# Sens_CC2D.net
KiCad netlist of a schematic drawn in EAGLE
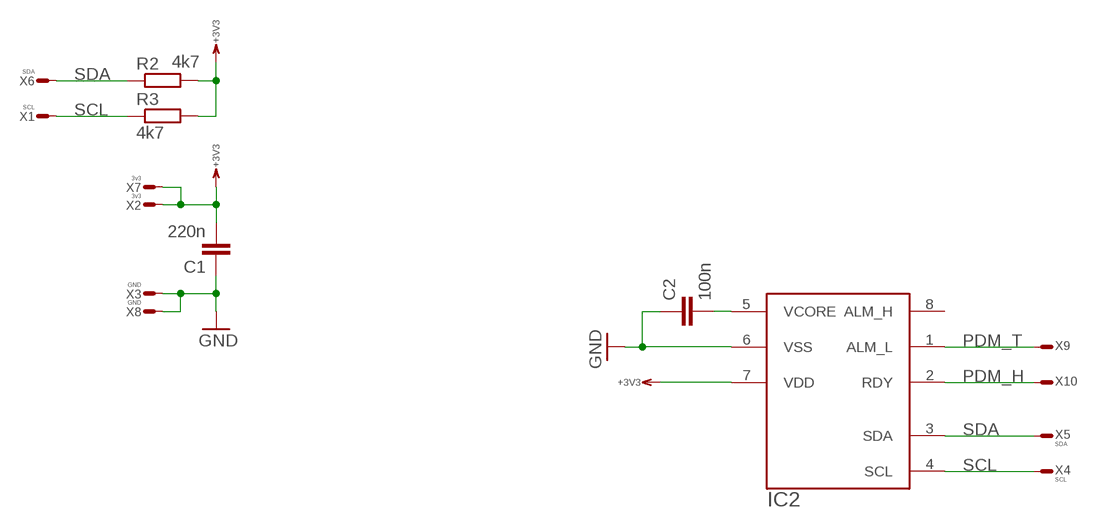
[diagram p0: schematic, sheet 1]

(export (version "E")
  (design (tool "Eeschema 10.0.6"))
  (components
    (comp (ref "C1")
      (value "220n")
      (footprint "eagle-import:0603")
      (libsource (lib "eagle-import") (part "C0603"))
    )
    (comp (ref "C2")
      (value "100n")
      (footprint "eagle-import:0603")
      (libsource (lib "eagle-import") (part "C0603"))
    )
    (comp (ref "IC2")
      (value "CC2D")
      (footprint "eagle-import:CC2D")
      (libsource (lib "eagle-import") (part "CC2D"))
    )
    (comp (ref "R2")
      (value "4k7")
      (footprint "eagle-import:0603")
      (libsource (lib "eagle-import") (part "R0603"))
    )
    (comp (ref "R3")
      (value "4k7")
      (footprint "eagle-import:0603")
      (libsource (lib "eagle-import") (part "R0603"))
    )
    (comp (ref "X1")
      (value "SCL")
      (footprint "eagle-import:T1.6_0.9")
      (libsource (lib "eagle-import") (part "WIREPADT1.6/0.9"))
    )
    (comp (ref "X2")
      (value "3v3")
      (footprint "eagle-import:T1.6_0.9")
      (libsource (lib "eagle-import") (part "WIREPADT1.6/0.9"))
    )
    (comp (ref "X3")
      (value "GND")
      (footprint "eagle-import:T1.6_0.9")
      (libsource (lib "eagle-import") (part "WIREPADT1.6/0.9"))
    )
    (comp (ref "X4")
      (value "SCL")
      (footprint "eagle-import:T1.6_0.9")
      (libsource (lib "eagle-import") (part "WIREPADT1.6/0.9"))
    )
    (comp (ref "X5")
      (value "SDA")
      (footprint "eagle-import:T1.6_0.9")
      (libsource (lib "eagle-import") (part "WIREPADT1.6/0.9"))
    )
    (comp (ref "X6")
      (value "SDA")
      (footprint "eagle-import:T1.6_0.9")
      (libsource (lib "eagle-import") (part "WIREPADT1.6/0.9"))
    )
    (comp (ref "X7")
      (value "3v3")
      (footprint "eagle-import:T1.6_0.9")
      (libsource (lib "eagle-import") (part "WIREPADT1.6/0.9"))
    )
    (comp (ref "X8")
      (value "GND")
      (footprint "eagle-import:T1.6_0.9")
      (libsource (lib "eagle-import") (part "WIREPADT1.6/0.9"))
    )
    (comp (ref "X9")
      (value "WIREPADR")
      (footprint "eagle-import:S1.27R")
      (libsource (lib "eagle-import") (part "WIREPADR"))
    )
    (comp (ref "X10")
      (value "WIREPADR")
      (footprint "eagle-import:S1.27R")
      (libsource (lib "eagle-import") (part "WIREPADR"))
    )
  )
  (nets
    (net (code "1") (name "+3V3") (class "Default")
      (node (ref "C1") (pin "2") (pinfunction "2_2") (pintype "passive"))
      (node (ref "IC2") (pin "7") (pinfunction "VDD_7") (pintype "bidirectional"))
      (node (ref "R2") (pin "2") (pinfunction "2_2") (pintype "passive"))
      (node (ref "R3") (pin "2") (pinfunction "2_2") (pintype "passive"))
      (node (ref "X2") (pin "1") (pinfunction "S_1") (pintype "passive"))
      (node (ref "X7") (pin "1") (pinfunction "S_1") (pintype "passive"))
    )
    (net (code "2") (name "/PDM_H") (class "Default")
      (node (ref "IC2") (pin "2") (pinfunction "RDY_2") (pintype "output"))
      (node (ref "X10") (pin "1") (pinfunction "S_1") (pintype "passive"))
    )
    (net (code "3") (name "/PDM_T") (class "Default")
      (node (ref "IC2") (pin "1") (pinfunction "ALM_L_1") (pintype "output"))
      (node (ref "X9") (pin "1") (pinfunction "S_1") (pintype "passive"))
    )
    (net (code "4") (name "/SCL") (class "Default")
      (node (ref "IC2") (pin "4") (pinfunction "SCL_4") (pintype "bidirectional"))
      (node (ref "R3") (pin "1") (pinfunction "1_1") (pintype "passive"))
      (node (ref "X1") (pin "1") (pinfunction "S_1") (pintype "passive"))
      (node (ref "X4") (pin "1") (pinfunction "S_1") (pintype "passive"))
    )
    (net (code "5") (name "/SDA") (class "Default")
      (node (ref "IC2") (pin "3") (pinfunction "SDA_3") (pintype "bidirectional"))
      (node (ref "R2") (pin "1") (pinfunction "1_1") (pintype "passive"))
      (node (ref "X5") (pin "1") (pinfunction "S_1") (pintype "passive"))
      (node (ref "X6") (pin "1") (pinfunction "S_1") (pintype "passive"))
    )
    (net (code "6") (name "GND") (class "Default")
      (node (ref "C1") (pin "1") (pinfunction "1_1") (pintype "passive"))
      (node (ref "C2") (pin "1") (pinfunction "1_1") (pintype "passive"))
      (node (ref "IC2") (pin "6") (pinfunction "VSS_6") (pintype "bidirectional"))
      (node (ref "X3") (pin "1") (pinfunction "S_1") (pintype "passive"))
      (node (ref "X8") (pin "1") (pinfunction "S_1") (pintype "passive"))
    )
    (net (code "7") (name "Net-(IC2-VCORE)") (class "Default")
      (node (ref "C2") (pin "2") (pinfunction "2_2") (pintype "passive"))
      (node (ref "IC2") (pin "5") (pinfunction "VCORE_5") (pintype "bidirectional"))
    )
    (net (code "8") (name "unconnected-(IC2-ALM_H-Pad8)") (class "Default")
      (node (ref "IC2") (pin "8") (pinfunction "ALM_H_8") (pintype "output"))
    )
  )
)
